# 01_MAIN.net
KiCad netlist of a schematic drawn in Altium Designer
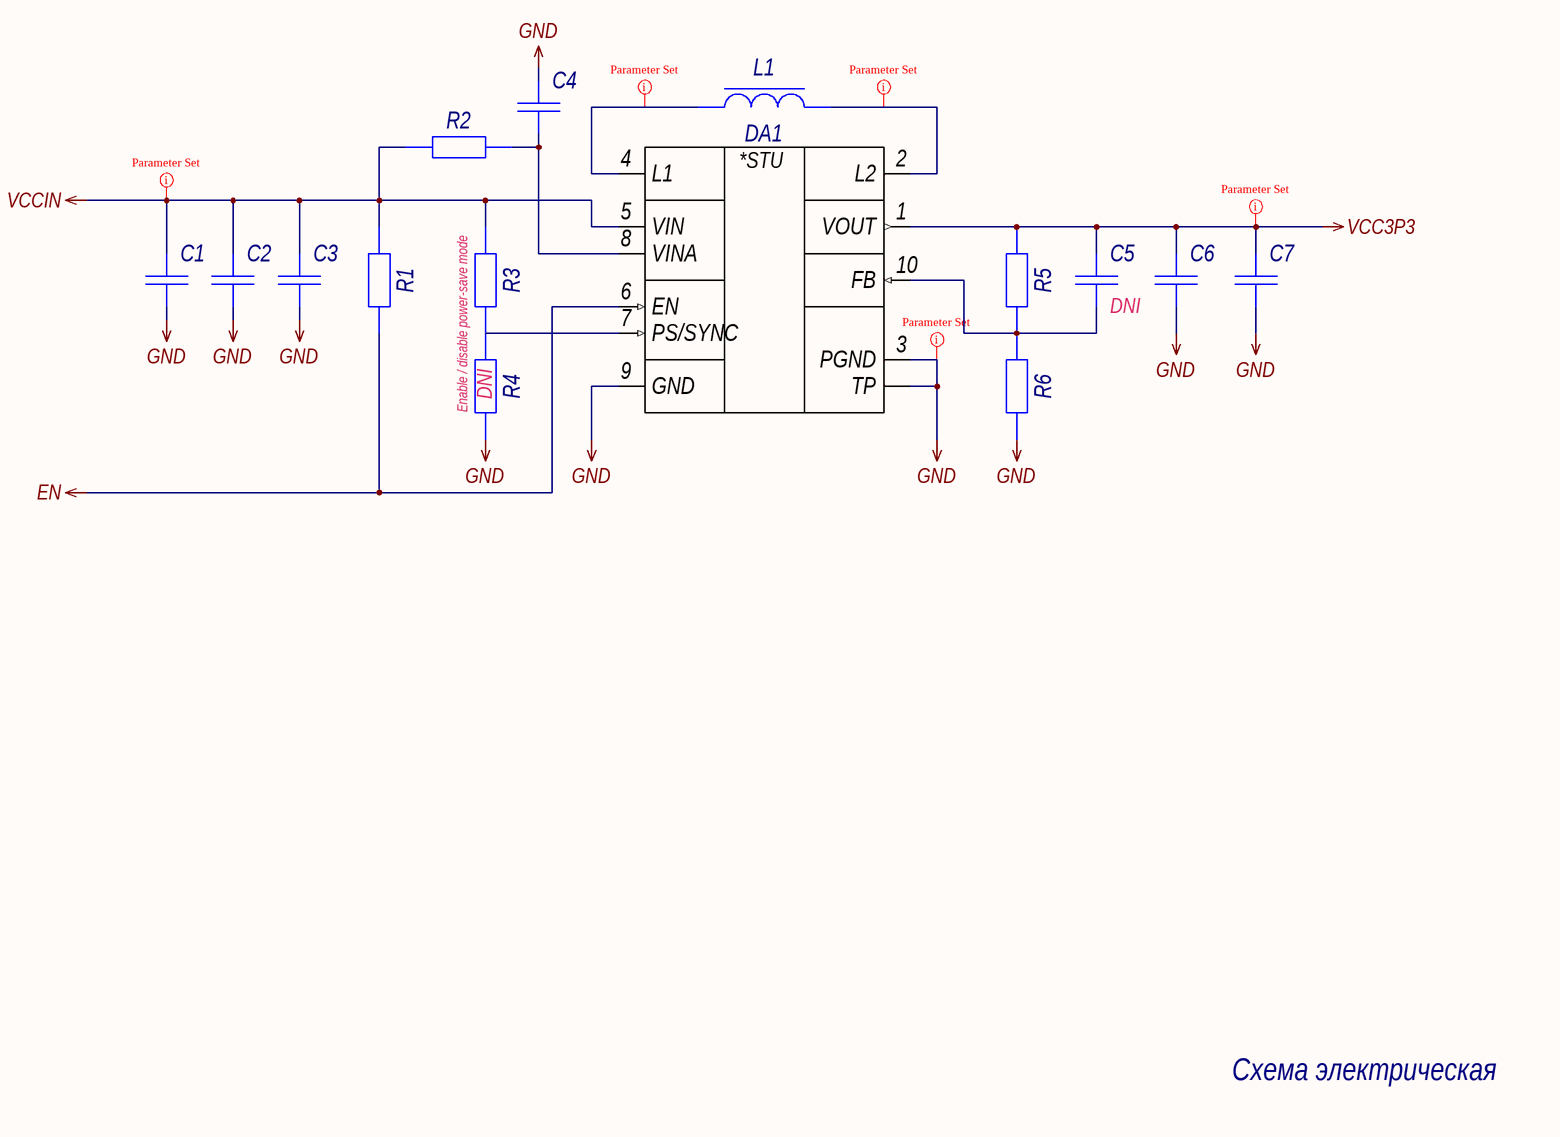
[diagram p0: 01_MAIN.SchDoc]

(export (version "E")
  (design (tool "Eeschema 10.0.6"))
  (components
    (comp (ref "C1")
      (value "Capacitor")
      (footprint "C0603_L")
      (fields
        (field (name "PART NUMBER") "GRM188R61E106MA73D")
        (field (name "VOLTAGE") "25V")
        (field (name "TOLERANCE") "±20%")
        (field (name "PUBLISHER") "Andrew Danich")
      )
      (libsource (lib "ADLib") (part "Capacitor"))
    )
    (comp (ref "C2")
      (value "Capacitor")
      (footprint "C0603_L")
      (fields
        (field (name "PART NUMBER") "GRM188R61E106MA73D")
        (field (name "VOLTAGE") "25V")
        (field (name "TOLERANCE") "±20%")
        (field (name "PUBLISHER") "Andrew Danich")
      )
      (libsource (lib "ADLib") (part "Capacitor"))
    )
    (comp (ref "C3")
      (value "Capacitor")
      (footprint "C0603_L")
      (fields
        (field (name "PART NUMBER") "GRM188R72A104KA35D")
        (field (name "VOLTAGE") "100V")
        (field (name "TOLERANCE") "±10%")
        (field (name "PUBLISHER") "Andrew Danich")
      )
      (libsource (lib "ADLib") (part "Capacitor"))
    )
    (comp (ref "C4")
      (value "Capacitor")
      (footprint "C0603_L")
      (fields
        (field (name "PART NUMBER") "GRM188R72A104KA35D")
        (field (name "VOLTAGE") "100V")
        (field (name "TOLERANCE") "±10%")
        (field (name "PUBLISHER") "Andrew Danich")
      )
      (libsource (lib "ADLib") (part "Capacitor"))
    )
    (comp (ref "C5")
      (value "Capacitor")
      (footprint "C0603_L")
      (fields
        (field (name "PART NUMBER") "GCM1885C2A101JA16D")
        (field (name "VOLTAGE") "100V")
        (field (name "TOLERANCE") "±5%")
        (field (name "PUBLISHER") "Andrew Danich")
      )
      (libsource (lib "ADLib") (part "Capacitor"))
    )
    (comp (ref "C6")
      (value "Capacitor")
      (footprint "C0603_L")
      (fields
        (field (name "PART NUMBER") "GRM188R61E106MA73D")
        (field (name "VOLTAGE") "25V")
        (field (name "TOLERANCE") "±20%")
        (field (name "PUBLISHER") "Andrew Danich")
      )
      (libsource (lib "ADLib") (part "Capacitor"))
    )
    (comp (ref "C7")
      (value "Capacitor")
      (footprint "C0603_L")
      (fields
        (field (name "PART NUMBER") "GRM188R61E106MA73D")
        (field (name "VOLTAGE") "25V")
        (field (name "TOLERANCE") "±20%")
        (field (name "PUBLISHER") "Andrew Danich")
      )
      (libsource (lib "ADLib") (part "Capacitor"))
    )
    (comp (ref "DA1")
      (value "TPS6300x")
      (footprint "VSON-10_050P300X300X100_N")
      (fields
        (field (name "PART NUMBER") "TPS63000DRCR")
        (field (name "MANUFACTURER") "Texas Instruments")
        (field (name "PUBLISHER") "Andrew Danich")
      )
      (libsource (lib "ADLib") (part "TPS6300x"))
    )
    (comp (ref "L1")
      (value "Coil")
      (footprint "LQH43CN-Series")
      (fields
        (field (name "PART NUMBER") "LQH43CN2R2M03L")
        (field (name "TOLERANCE") "±20%")
        (field (name "MANUFACTURER") "Murata Electronics")
        (field (name "PUBLISHER") "Andrew Danich")
      )
      (libsource (lib "ADLib") (part "Coil"))
    )
    (comp (ref "R1")
      (value "Resistor")
      (footprint "R0603_L")
      (fields
        (field (name "PART NUMBER") "RC0603JR-070R")
        (field (name "TOLERANCE") "±5%")
        (field (name "MANUFACTURER") "Yageo")
        (field (name "PUBLISHER") "Andrew Danich")
      )
      (libsource (lib "ADLib") (part "Resistor"))
    )
    (comp (ref "R2")
      (value "Resistor")
      (footprint "R0603_L")
      (fields
        (field (name "PART NUMBER") "RC0603JR-07100R")
        (field (name "TOLERANCE") "±5%")
        (field (name "MANUFACTURER") "Yageo")
        (field (name "PUBLISHER") "Andrew Danich")
      )
      (libsource (lib "ADLib") (part "Resistor"))
    )
    (comp (ref "R3")
      (value "Resistor")
      (footprint "R0603_L")
      (fields
        (field (name "PART NUMBER") "RC0603JR-070R")
        (field (name "TOLERANCE") "±5%")
        (field (name "MANUFACTURER") "Yageo")
        (field (name "PUBLISHER") "Andrew Danich")
      )
      (libsource (lib "ADLib") (part "Resistor"))
    )
    (comp (ref "R4")
      (value "Resistor")
      (footprint "R0603_L")
      (fields
        (field (name "PART NUMBER") "RC0603JR-070R")
        (field (name "TOLERANCE") "±5%")
        (field (name "MANUFACTURER") "Yageo")
        (field (name "PUBLISHER") "Andrew Danich")
      )
      (libsource (lib "ADLib") (part "Resistor"))
    )
    (comp (ref "R5")
      (value "Resistor")
      (footprint "R0603_L")
      (fields
        (field (name "PART NUMBER") "RC0603JR-071ML")
        (field (name "TOLERANCE") "±5%")
        (field (name "MANUFACTURER") "Yageo")
        (field (name "PUBLISHER") "Andrew Danich")
      )
      (libsource (lib "ADLib") (part "Resistor"))
    )
    (comp (ref "R6")
      (value "Resistor")
      (footprint "R0603_L")
      (fields
        (field (name "PART NUMBER") "RC0603JR-07180KL")
        (field (name "TOLERANCE") "±5%")
        (field (name "MANUFACTURER") "Yageo")
        (field (name "PUBLISHER") "Andrew Danich")
      )
      (libsource (lib "ADLib") (part "Resistor"))
    )
  )
  (nets
    (net (code "1") (name "EN") (class "Default")
      (node (ref "DA1") (pin "6") (pinfunction "EN_6") (pintype "input"))
      (node (ref "R1") (pin "1") (pinfunction "1_1") (pintype "passive"))
    )
    (net (code "2") (name "GND") (class "Default")
      (node (ref "C1") (pin "1") (pinfunction "1_1") (pintype "passive"))
      (node (ref "C2") (pin "1") (pinfunction "1_1") (pintype "passive"))
      (node (ref "C3") (pin "1") (pinfunction "1_1") (pintype "passive"))
      (node (ref "C4") (pin "2") (pinfunction "2_2") (pintype "passive"))
      (node (ref "C6") (pin "1") (pinfunction "1_1") (pintype "passive"))
      (node (ref "C7") (pin "1") (pinfunction "1_1") (pintype "passive"))
      (node (ref "DA1") (pin "3") (pinfunction "PGND_3") (pintype "power_in"))
      (node (ref "DA1") (pin "9") (pinfunction "GND_9") (pintype "power_in"))
      (node (ref "DA1") (pin "TP") (pinfunction "TP_TP") (pintype "passive"))
      (node (ref "R4") (pin "1") (pinfunction "1_1") (pintype "passive"))
      (node (ref "R6") (pin "1") (pinfunction "1_1") (pintype "passive"))
    )
    (net (code "3") (name "Net-(DA1-FB)") (class "Default")
      (node (ref "C5") (pin "1") (pinfunction "1_1") (pintype "passive"))
      (node (ref "DA1") (pin "10") (pinfunction "FB_10") (pintype "input"))
      (node (ref "R5") (pin "1") (pinfunction "1_1") (pintype "passive"))
      (node (ref "R6") (pin "2") (pinfunction "2_2") (pintype "passive"))
    )
    (net (code "4") (name "Net-(DA1-L1)") (class "Default")
      (node (ref "DA1") (pin "4") (pinfunction "L1_4") (pintype "passive"))
      (node (ref "L1") (pin "1") (pinfunction "1_1") (pintype "passive"))
    )
    (net (code "5") (name "Net-(DA1-L2)") (class "Default")
      (node (ref "DA1") (pin "2") (pinfunction "L2_2") (pintype "passive"))
      (node (ref "L1") (pin "2") (pinfunction "2_2") (pintype "passive"))
    )
    (net (code "6") (name "Net-(DA1-PS{slash}SYNC)") (class "Default")
      (node (ref "DA1") (pin "7") (pinfunction "PS/SYNC_7") (pintype "input"))
      (node (ref "R3") (pin "1") (pinfunction "1_1") (pintype "passive"))
      (node (ref "R4") (pin "2") (pinfunction "2_2") (pintype "passive"))
    )
    (net (code "7") (name "Net-(DA1-VINA)") (class "Default")
      (node (ref "C4") (pin "1") (pinfunction "1_1") (pintype "passive"))
      (node (ref "DA1") (pin "8") (pinfunction "VINA_8") (pintype "power_in"))
      (node (ref "R2") (pin "2") (pinfunction "2_2") (pintype "passive"))
    )
    (net (code "8") (name "VCC3P3") (class "Default")
      (node (ref "C5") (pin "2") (pinfunction "2_2") (pintype "passive"))
      (node (ref "C6") (pin "2") (pinfunction "2_2") (pintype "passive"))
      (node (ref "C7") (pin "2") (pinfunction "2_2") (pintype "passive"))
      (node (ref "DA1") (pin "1") (pinfunction "VOUT_1") (pintype "output"))
      (node (ref "R5") (pin "2") (pinfunction "2_2") (pintype "passive"))
    )
    (net (code "9") (name "VCCIN") (class "Default")
      (node (ref "C1") (pin "2") (pinfunction "2_2") (pintype "passive"))
      (node (ref "C2") (pin "2") (pinfunction "2_2") (pintype "passive"))
      (node (ref "C3") (pin "2") (pinfunction "2_2") (pintype "passive"))
      (node (ref "DA1") (pin "5") (pinfunction "VIN_5") (pintype "power_in"))
      (node (ref "R1") (pin "2") (pinfunction "2_2") (pintype "passive"))
      (node (ref "R2") (pin "1") (pinfunction "1_1") (pintype "passive"))
      (node (ref "R3") (pin "2") (pinfunction "2_2") (pintype "passive"))
    )
  )
)
